# IN12_nixietube_module.net
KiCad netlist of a schematic drawn in EAGLE
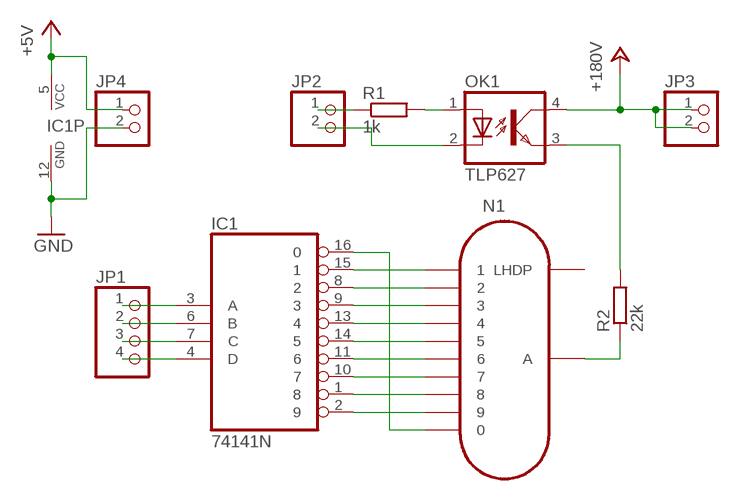
[diagram p0: schematic, sheet 1]

(export (version "E")
  (design (tool "Eeschema 10.0.6"))
  (components
    (comp (ref "IC1")
      (value "74141N")
      (footprint "eagle-import:DIL16")
      (libsource (lib "eagle-import") (part "74141N"))
    )
    (comp (ref "JP1")
      (value "PINHD-1X4")
      (footprint "eagle-import:1X04")
      (libsource (lib "eagle-import") (part "PINHD-1X4"))
    )
    (comp (ref "JP2")
      (value "PINHD-1X2")
      (footprint "eagle-import:1X02")
      (libsource (lib "eagle-import") (part "PINHD-1X2"))
    )
    (comp (ref "JP3")
      (value "PINHD-1X2")
      (footprint "eagle-import:1X02")
      (libsource (lib "eagle-import") (part "PINHD-1X2"))
    )
    (comp (ref "JP4")
      (value "PINHD-1X2")
      (footprint "eagle-import:1X02")
      (libsource (lib "eagle-import") (part "PINHD-1X2"))
    )
    (comp (ref "N1")
      (value "IN-12B")
      (footprint "eagle-import:IN-12")
      (libsource (lib "eagle-import") (part "IN-12B"))
    )
    (comp (ref "OK1")
      (value "TLP627")
      (footprint "eagle-import:4-SMD")
      (libsource (lib "eagle-import") (part "TLP627"))
    )
    (comp (ref "R1")
      (value "1k")
      (footprint "eagle-import:R0805")
      (libsource (lib "eagle-import") (part "R-EU_R0805"))
    )
    (comp (ref "R2")
      (value "22k")
      (footprint "eagle-import:0207_10")
      (libsource (lib "eagle-import") (part "R-EU_10"))
    )
  )
  (nets
    (net (code "1") (name "+5V") (class "Default")
      (node (ref "IC1") (pin "5") (pinfunction "VCC_5") (pintype "power_in"))
      (node (ref "JP4") (pin "1") (pinfunction "1_1") (pintype "passive"))
    )
    (net (code "2") (name "+180V") (class "Default")
      (node (ref "JP3") (pin "1") (pinfunction "1_1") (pintype "passive"))
      (node (ref "JP3") (pin "2") (pinfunction "2_2") (pintype "passive"))
      (node (ref "OK1") (pin "4") (pinfunction "COL_4") (pintype "passive"))
    )
    (net (code "3") (name "GND") (class "Default")
      (node (ref "IC1") (pin "12") (pinfunction "GND_12") (pintype "power_in"))
      (node (ref "JP4") (pin "2") (pinfunction "2_2") (pintype "passive"))
    )
    (net (code "4") (name "Net-(IC1A-0)") (class "Default")
      (node (ref "IC1") (pin "16") (pinfunction "0_16") (pintype "open_collector"))
      (node (ref "N1") (pin "0") (pinfunction "0_0") (pintype "bidirectional"))
    )
    (net (code "5") (name "Net-(IC1A-1)") (class "Default")
      (node (ref "IC1") (pin "15") (pinfunction "1_15") (pintype "open_collector"))
      (node (ref "N1") (pin "1") (pinfunction "1_1") (pintype "bidirectional"))
    )
    (net (code "6") (name "Net-(IC1A-2)") (class "Default")
      (node (ref "IC1") (pin "8") (pinfunction "2_8") (pintype "open_collector"))
      (node (ref "N1") (pin "2") (pinfunction "2_2") (pintype "bidirectional"))
    )
    (net (code "7") (name "Net-(IC1A-3)") (class "Default")
      (node (ref "IC1") (pin "9") (pinfunction "3_9") (pintype "open_collector"))
      (node (ref "N1") (pin "3") (pinfunction "3_3") (pintype "bidirectional"))
    )
    (net (code "8") (name "Net-(IC1A-4)") (class "Default")
      (node (ref "IC1") (pin "13") (pinfunction "4_13") (pintype "open_collector"))
      (node (ref "N1") (pin "4") (pinfunction "4_4") (pintype "bidirectional"))
    )
    (net (code "9") (name "Net-(IC1A-5)") (class "Default")
      (node (ref "IC1") (pin "14") (pinfunction "5_14") (pintype "open_collector"))
      (node (ref "N1") (pin "5") (pinfunction "5_5") (pintype "bidirectional"))
    )
    (net (code "10") (name "Net-(IC1A-6)") (class "Default")
      (node (ref "IC1") (pin "11") (pinfunction "6_11") (pintype "open_collector"))
      (node (ref "N1") (pin "6") (pinfunction "6_6") (pintype "bidirectional"))
    )
    (net (code "11") (name "Net-(IC1A-7)") (class "Default")
      (node (ref "IC1") (pin "10") (pinfunction "7_10") (pintype "open_collector"))
      (node (ref "N1") (pin "7") (pinfunction "7_7") (pintype "bidirectional"))
    )
    (net (code "12") (name "Net-(IC1A-8)") (class "Default")
      (node (ref "IC1") (pin "1") (pinfunction "8_1") (pintype "open_collector"))
      (node (ref "N1") (pin "8") (pinfunction "8_8") (pintype "bidirectional"))
    )
    (net (code "13") (name "Net-(IC1A-9)") (class "Default")
      (node (ref "IC1") (pin "2") (pinfunction "9_2") (pintype "open_collector"))
      (node (ref "N1") (pin "9") (pinfunction "9_9") (pintype "bidirectional"))
    )
    (net (code "14") (name "Net-(IC1A-A)") (class "Default")
      (node (ref "IC1") (pin "3") (pinfunction "A_3") (pintype "input"))
      (node (ref "JP1") (pin "1") (pinfunction "1_1") (pintype "passive"))
    )
    (net (code "15") (name "Net-(IC1A-B)") (class "Default")
      (node (ref "IC1") (pin "6") (pinfunction "B_6") (pintype "input"))
      (node (ref "JP1") (pin "2") (pinfunction "2_2") (pintype "passive"))
    )
    (net (code "16") (name "Net-(IC1A-C)") (class "Default")
      (node (ref "IC1") (pin "7") (pinfunction "C_7") (pintype "input"))
      (node (ref "JP1") (pin "3") (pinfunction "3_3") (pintype "passive"))
    )
    (net (code "17") (name "Net-(IC1A-D)") (class "Default")
      (node (ref "IC1") (pin "4") (pinfunction "D_4") (pintype "input"))
      (node (ref "JP1") (pin "4") (pinfunction "4_4") (pintype "passive"))
    )
    (net (code "18") (name "Net-(JP2-Pad1)") (class "Default")
      (node (ref "JP2") (pin "1") (pinfunction "1_1") (pintype "passive"))
      (node (ref "R1") (pin "1") (pinfunction "1_1") (pintype "passive"))
    )
    (net (code "19") (name "Net-(N1-PadA)") (class "Default")
      (node (ref "N1") (pin "A") (pinfunction "A_A") (pintype "bidirectional"))
      (node (ref "R2") (pin "1") (pinfunction "1_1") (pintype "passive"))
    )
    (net (code "20") (name "Net-(OK1-A)") (class "Default")
      (node (ref "OK1") (pin "1") (pinfunction "A_1") (pintype "passive"))
      (node (ref "R1") (pin "2") (pinfunction "2_2") (pintype "passive"))
    )
    (net (code "21") (name "Net-(OK1-C)") (class "Default")
      (node (ref "JP2") (pin "2") (pinfunction "2_2") (pintype "passive"))
      (node (ref "OK1") (pin "2") (pinfunction "C_2") (pintype "passive"))
    )
    (net (code "22") (name "Net-(OK1-EMIT)") (class "Default")
      (node (ref "OK1") (pin "3") (pinfunction "EMIT_3") (pintype "passive"))
      (node (ref "R2") (pin "2") (pinfunction "2_2") (pintype "passive"))
    )
    (net (code "23") (name "unconnected-(N1-PadLHDP)") (class "Default")
      (node (ref "N1") (pin "LHDP") (pinfunction "LHDP_LHDP") (pintype "bidirectional"))
    )
  )
)
